# Automatic_Water_Level_Controller_-_Copy.net
KiCad netlist of a schematic drawn in Altium Designer
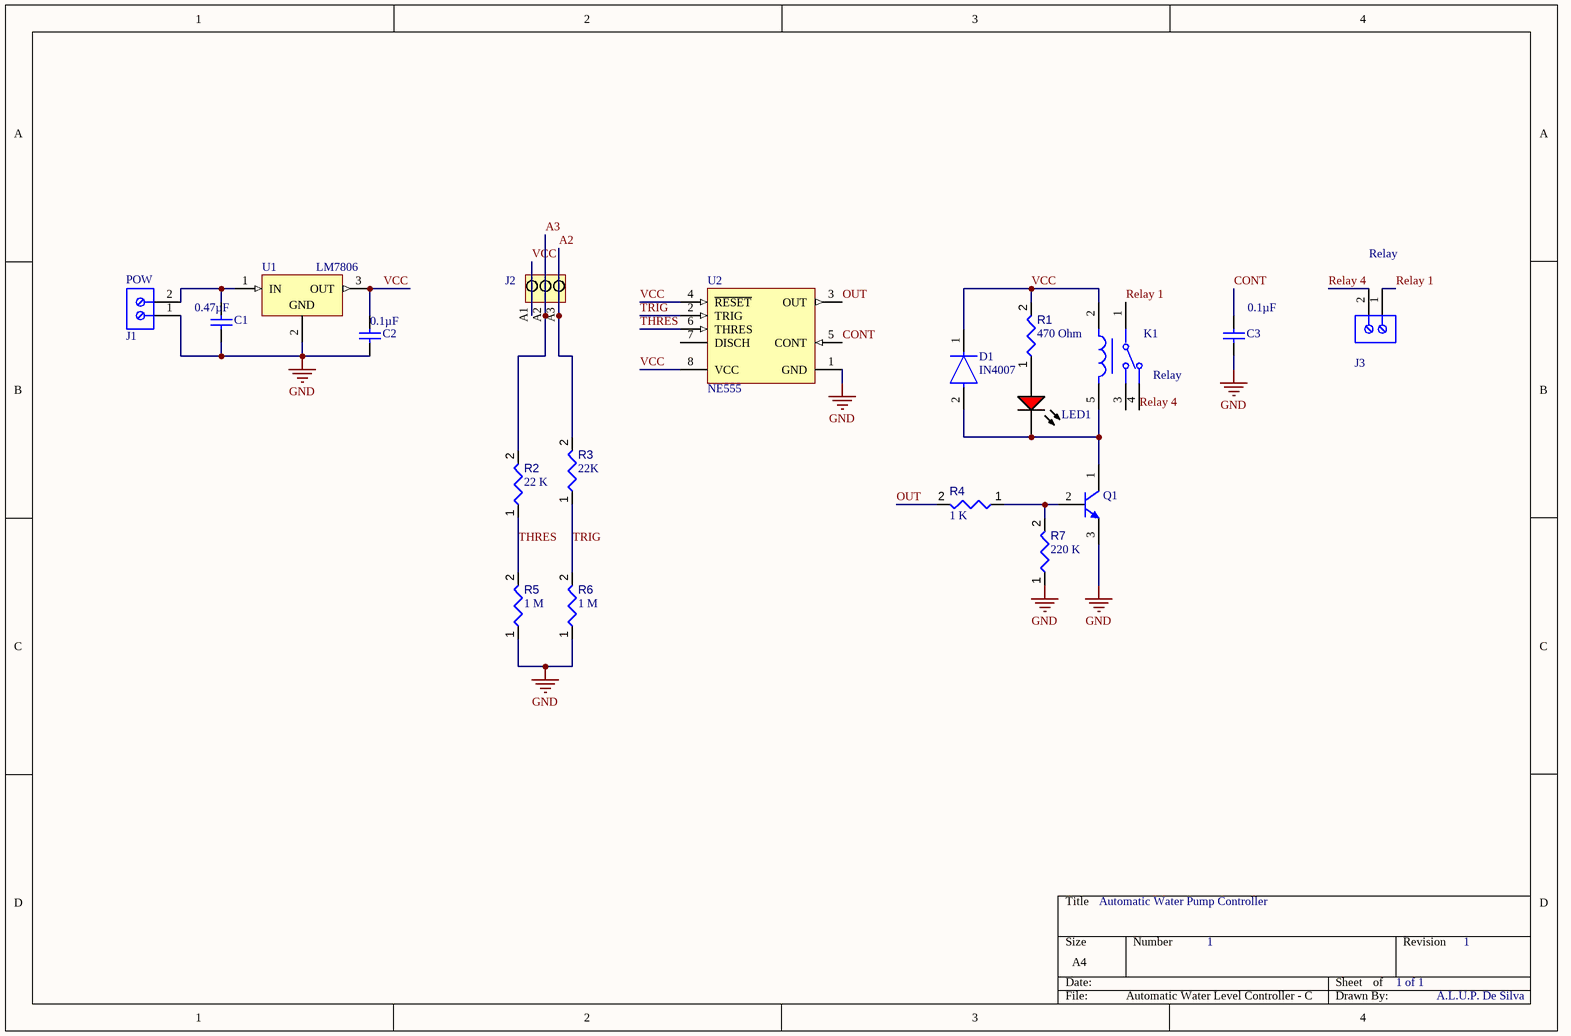
[diagram p0: Automatic Water Level Controller - Copy.SchDoc]

(export (version "E")
  (design (tool "Eeschema 10.0.6"))
  (components
    (comp (ref "C1")
      (value "C330C105M5U5TA")
      (footprint "KEMT-C330C105M5U5TA")
      (description "Ceramic Capacitor, 1 uF, +/- 20%, 50 V, -10 to 85 degC, 2-Pin THD, RoHS, Bulk")
      (fields
        (field (name "TOLERANCE") "±20%")
        (field (name "CAPACITANCE") "0.47µF")
        (field (name "MANUFACTURER") "Kemet")
      )
      (libsource (lib "Altium Content Vault") (part "CAP-NP-2"))
    )
    (comp (ref "C2")
      (value "C330C105M5U5TA")
      (footprint "KEMT-C330C105M5U5TA")
      (description "Ceramic Capacitor, 1 uF, +/- 20%, 50 V, -10 to 85 degC, 2-Pin THD, RoHS, Bulk")
      (fields
        (field (name "TOLERANCE") "±20%")
        (field (name "CAPACITANCE") "0.1µF")
        (field (name "MANUFACTURER") "Kemet")
      )
      (libsource (lib "Altium Content Vault") (part "CAP-NP-2"))
    )
    (comp (ref "C3")
      (value "K104K15X7RF5TL2")
      (footprint "VISH-K104K15X7RF5TL2")
      (description "Ceramic Capacitor, 100 nF, +/- 10%, 50 V, -55 to 125 degC, 2-Pin THD, RoHS, Tape and Reel")
      (fields
        (field (name "MANUFACTURER") "Vishay")
        (field (name "TOLERANCE") "±10%")
        (field (name "CAPACITANCE") "0.1µF")
      )
      (libsource (lib "Altium Content Vault") (part "CAP-NP-2"))
    )
    (comp (ref "D1")
      (value "IN4007")
      (footprint "FP-1N4007-MFG")
      (description "DIODE GEN PURP 1KV 1A DO204AL")
      (fields
        (field (name "OCTOPART") "https://octopart.com/1n4007-e3%2F54-vishay-39548207")
        (field (name "MANUFACTURER") "Vishay")
      )
      (libsource (lib "Altium Content Vault") (part "d7152d700b627762746794eb795d46e"))
    )
    (comp (ref "J1")
      (value "POW")
      (footprint "691102710002")
      (description "Series 102 - 5.00 mm Horizontal Entry Modular with Pressure Clamp WR-TBL, 2 pin")
      (fields
        (field (name "MANUFACTURER") "Wurth Elektronik")
        (field (name "PART NUMBER") "691102710002")
        (field (name "PUBLISHER") "WurthElektronik")
      )
      (libsource (lib "Altium Content Vault") (part "WE-CN-1P-F-TB2"))
    )
    (comp (ref "J2")
      (value "1715320000")
      (footprint "LM_5_00_90_03")
      (description "OMNIMATE Signal - series LM")
      (fields (field (name "MANUFACTURER") "Weidmueller"))
      (libsource (lib "Altium Content Vault") (part "Terminal_03_1x03"))
    )
    (comp (ref "J3")
      (value "Relay")
      (footprint "691102710002")
      (description "Series 102 - 5.00 mm Horizontal Entry Modular with Pressure Clamp WR-TBL, 2 pin")
      (fields
        (field (name "MANUFACTURER") "Wurth Elektronik")
        (field (name "PART NUMBER") "691102710002")
        (field (name "PUBLISHER") "WurthElektronik")
      )
      (libsource (lib "Altium Content Vault") (part "WE-CN-1P-F-TB2"))
    )
    (comp (ref "K1")
      (value "Relay")
      (footprint "FP-G5LE-14-DC5-MFG")
      (description "RELAY GEN PURPOSE SPDT 10A 5V")
      (fields
        (field (name "OCTOPART") "https://octopart.com/g5le-14-dc5-omron-28829")
        (field (name "MANUFACTURER") "Omron")
      )
      (libsource (lib "Altium Content Vault") (part "c03b8d08e5d02e70a6880f365e34168"))
    )
    (comp (ref "LED1")
      (value "HLMP-3301")
      (footprint "AVAG-HLMP-3301-2")
      (description "T-1 3/4 (5 mm) Diffused LED Lamp, 1.9 V, -40 to 100 degC, 2-Pin THD, RoHS, Bulk")
      (fields (field (name "MANUFACTURER") "Avago"))
      (libsource (lib "Altium Content Vault") (part "LED-RED-K1A2-2"))
    )
    (comp (ref "Q1")
      (value "BC547BRL1G")
      (footprint "ONSC-TO-92-3-29-11_AM_BL")
      (description "Amplifier Transistor, NPN Silicon, 3-Pin TO-92, Pb-Free, Tape and Reel")
      (fields (field (name "MANUFACTURER") "On Semiconductor"))
      (libsource (lib "Altium Content Vault") (part "ONSC-NPN-C1B2E3-3"))
    )
    (comp (ref "R1")
      (value "470 Ohm")
      (footprint "RESA60-630X240")
      (description "Axial Resistor, 475 KOhm, +/- 1%, 0.25 W, -55 to 155 degC, 2-Pin THD, RoHS, Bulk")
      (fields (field (name "POWER") "250mW") (field (name "TOLERANCE") "1%"))
      (libsource (lib "Ulindu's Workspace") (part "RES-2"))
    )
    (comp (ref "R2")
      (value "22 K")
      (footprint "RESA60-630X240")
      (description "Axial Resistor, 475 KOhm, +/- 1%, 0.25 W, -55 to 155 degC, 2-Pin THD, RoHS, Bulk")
      (fields (field (name "POWER") "250mW") (field (name "TOLERANCE") "1%"))
      (libsource (lib "Ulindu's Workspace") (part "RES-2"))
    )
    (comp (ref "R3")
      (value "22K")
      (footprint "RESA60-630X240")
      (description "Axial Resistor, 475 KOhm, +/- 1%, 0.25 W, -55 to 155 degC, 2-Pin THD, RoHS, Bulk")
      (fields (field (name "POWER") "250mW") (field (name "TOLERANCE") "1%"))
      (libsource (lib "Ulindu's Workspace") (part "RES-2"))
    )
    (comp (ref "R4")
      (value "1 K")
      (footprint "RESA60-630X240")
      (description "Axial Resistor, 475 KOhm, +/- 1%, 0.25 W, -55 to 155 degC, 2-Pin THD, RoHS, Bulk")
      (fields (field (name "POWER") "250mW") (field (name "TOLERANCE") "1%"))
      (libsource (lib "Ulindu's Workspace") (part "RES-2"))
    )
    (comp (ref "R5")
      (value "1 M")
      (footprint "RESA60-630X240")
      (description "Axial Resistor, 475 KOhm, +/- 1%, 0.25 W, -55 to 155 degC, 2-Pin THD, RoHS, Bulk")
      (fields (field (name "POWER") "250mW") (field (name "TOLERANCE") "1%"))
      (libsource (lib "Ulindu's Workspace") (part "RES-2"))
    )
    (comp (ref "R6")
      (value "1 M")
      (footprint "RESA60-630X240")
      (description "Axial Resistor, 475 KOhm, +/- 1%, 0.25 W, -55 to 155 degC, 2-Pin THD, RoHS, Bulk")
      (fields (field (name "POWER") "250mW") (field (name "TOLERANCE") "1%"))
      (libsource (lib "Ulindu's Workspace") (part "RES-2"))
    )
    (comp (ref "R7")
      (value "220 K")
      (footprint "RESA60-630X240")
      (description "Axial Resistor, 475 KOhm, +/- 1%, 0.25 W, -55 to 155 degC, 2-Pin THD, RoHS, Bulk")
      (fields (field (name "POWER") "250mW") (field (name "TOLERANCE") "1%"))
      (libsource (lib "Ulindu's Workspace") (part "RES-2"))
    )
    (comp (ref "U1")
      (value "LM7806")
      (footprint "FAIR-TO-220-3")
      (description "Positive Voltage Regulator, 5 V, 1 A, -40 to 125 degC, 3-Pin TO-220, RoHS, Tube")
      (fields (field (name "MANUFACTURER") "FairchildSemiconductor"))
      (libsource (lib "Altium Content Vault") (part "FAIR-LM7805CT-TO220-3"))
    )
    (comp (ref "U2")
      (value "NE555")
      (footprint "P0008A")
      (description "Precision Timer, 4.5 to 16 V, 0 to 70 degC, 8-Pin DIP, Pb-Free, Tube")
      (fields (field (name "MANUFACTURER") "TexasInstruments"))
      (libsource (lib "Altium Content Vault") (part "TI-NE555-P8"))
    )
  )
  (nets
    (net (code "1") (name "/A2") (class "Default")
      (node (ref "J2") (pin "A3") (pinfunction "A3_A3") (pintype "passive"))
      (node (ref "R3") (pin "2") (pinfunction "2_2") (pintype "passive"))
    )
    (net (code "2") (name "/A3") (class "Default")
      (node (ref "J2") (pin "A2") (pinfunction "A2_A2") (pintype "passive"))
      (node (ref "R2") (pin "2") (pinfunction "2_2") (pintype "passive"))
    )
    (net (code "3") (name "/CONT") (class "Default")
      (node (ref "C3") (pin "2") (pinfunction "2_2") (pintype "passive"))
      (node (ref "U2") (pin "5") (pinfunction "CONT_5") (pintype "input"))
    )
    (net (code "4") (name "/OUT") (class "Default")
      (node (ref "R4") (pin "2") (pinfunction "2_2") (pintype "passive"))
      (node (ref "U2") (pin "3") (pinfunction "OUT_3") (pintype "output"))
    )
    (net (code "5") (name "/Relay 1") (class "Default")
      (node (ref "J3") (pin "1") (pinfunction "1_1") (pintype "passive"))
      (node (ref "K1") (pin "1") (pinfunction "1_1") (pintype "passive"))
    )
    (net (code "6") (name "/Relay 4") (class "Default")
      (node (ref "J3") (pin "2") (pinfunction "2_2") (pintype "passive"))
      (node (ref "K1") (pin "4") (pinfunction "4_4") (pintype "passive"))
    )
    (net (code "7") (name "/THRES") (class "Default")
      (node (ref "R2") (pin "1") (pinfunction "1_1") (pintype "passive"))
      (node (ref "R5") (pin "2") (pinfunction "2_2") (pintype "passive"))
      (node (ref "U2") (pin "6") (pinfunction "THRES_6") (pintype "input"))
    )
    (net (code "8") (name "/TRIG") (class "Default")
      (node (ref "R3") (pin "1") (pinfunction "1_1") (pintype "passive"))
      (node (ref "R6") (pin "2") (pinfunction "2_2") (pintype "passive"))
      (node (ref "U2") (pin "2") (pinfunction "TRIG_2") (pintype "input"))
    )
    (net (code "9") (name "/VCC") (class "Default")
      (node (ref "C2") (pin "2") (pinfunction "2_2") (pintype "passive"))
      (node (ref "D1") (pin "1") (pinfunction "C_1") (pintype "passive"))
      (node (ref "J2") (pin "A1") (pinfunction "A1_A1") (pintype "passive"))
      (node (ref "K1") (pin "2") (pinfunction "2_2") (pintype "passive"))
      (node (ref "R1") (pin "2") (pinfunction "2_2") (pintype "passive"))
      (node (ref "U1") (pin "3") (pinfunction "OUT_3") (pintype "output"))
      (node (ref "U2") (pin "4") (pinfunction "~{RESET}_4") (pintype "input"))
      (node (ref "U2") (pin "8") (pinfunction "VCC_8") (pintype "power_in"))
    )
    (net (code "10") (name "GND") (class "Default")
      (node (ref "C1") (pin "1") (pinfunction "1_1") (pintype "passive"))
      (node (ref "C2") (pin "1") (pinfunction "1_1") (pintype "passive"))
      (node (ref "C3") (pin "1") (pinfunction "1_1") (pintype "passive"))
      (node (ref "J1") (pin "1") (pinfunction "1_1") (pintype "passive"))
      (node (ref "Q1") (pin "3") (pinfunction "E_3") (pintype "passive"))
      (node (ref "R5") (pin "1") (pinfunction "1_1") (pintype "passive"))
      (node (ref "R6") (pin "1") (pinfunction "1_1") (pintype "passive"))
      (node (ref "R7") (pin "1") (pinfunction "1_1") (pintype "passive"))
      (node (ref "U1") (pin "2") (pinfunction "GND_2") (pintype "power_in"))
      (node (ref "U2") (pin "1") (pinfunction "GND_1") (pintype "power_in"))
    )
    (net (code "11") (name "Net-(D1-A)") (class "Default")
      (node (ref "D1") (pin "2") (pinfunction "A_2") (pintype "passive"))
      (node (ref "K1") (pin "5") (pinfunction "5_5") (pintype "passive"))
      (node (ref "LED1") (pin "1") (pinfunction "K_1") (pintype "passive"))
      (node (ref "Q1") (pin "1") (pinfunction "C_1") (pintype "passive"))
    )
    (net (code "12") (name "Net-(LED1-A)") (class "Default")
      (node (ref "LED1") (pin "2") (pinfunction "A_2") (pintype "passive"))
      (node (ref "R1") (pin "1") (pinfunction "1_1") (pintype "passive"))
    )
    (net (code "13") (name "Net-(Q1-B)") (class "Default")
      (node (ref "Q1") (pin "2") (pinfunction "B_2") (pintype "passive"))
      (node (ref "R4") (pin "1") (pinfunction "1_1") (pintype "passive"))
      (node (ref "R7") (pin "2") (pinfunction "2_2") (pintype "passive"))
    )
    (net (code "14") (name "Net-(U1-IN)") (class "Default")
      (node (ref "C1") (pin "2") (pinfunction "2_2") (pintype "passive"))
      (node (ref "J1") (pin "2") (pinfunction "2_2") (pintype "passive"))
      (node (ref "U1") (pin "1") (pinfunction "IN_1") (pintype "input"))
    )
    (net (code "15") (name "unconnected-(K1-Pad3)") (class "Default")
      (node (ref "K1") (pin "3") (pinfunction "3_3") (pintype "passive"))
    )
    (net (code "16") (name "unconnected-(U2-DISCH-Pad7)") (class "Default")
      (node (ref "U2") (pin "7") (pinfunction "DISCH_7") (pintype "open_collector"))
    )
  )
)
